# 32u4_board.net
KiCad netlist of a schematic drawn in EAGLE
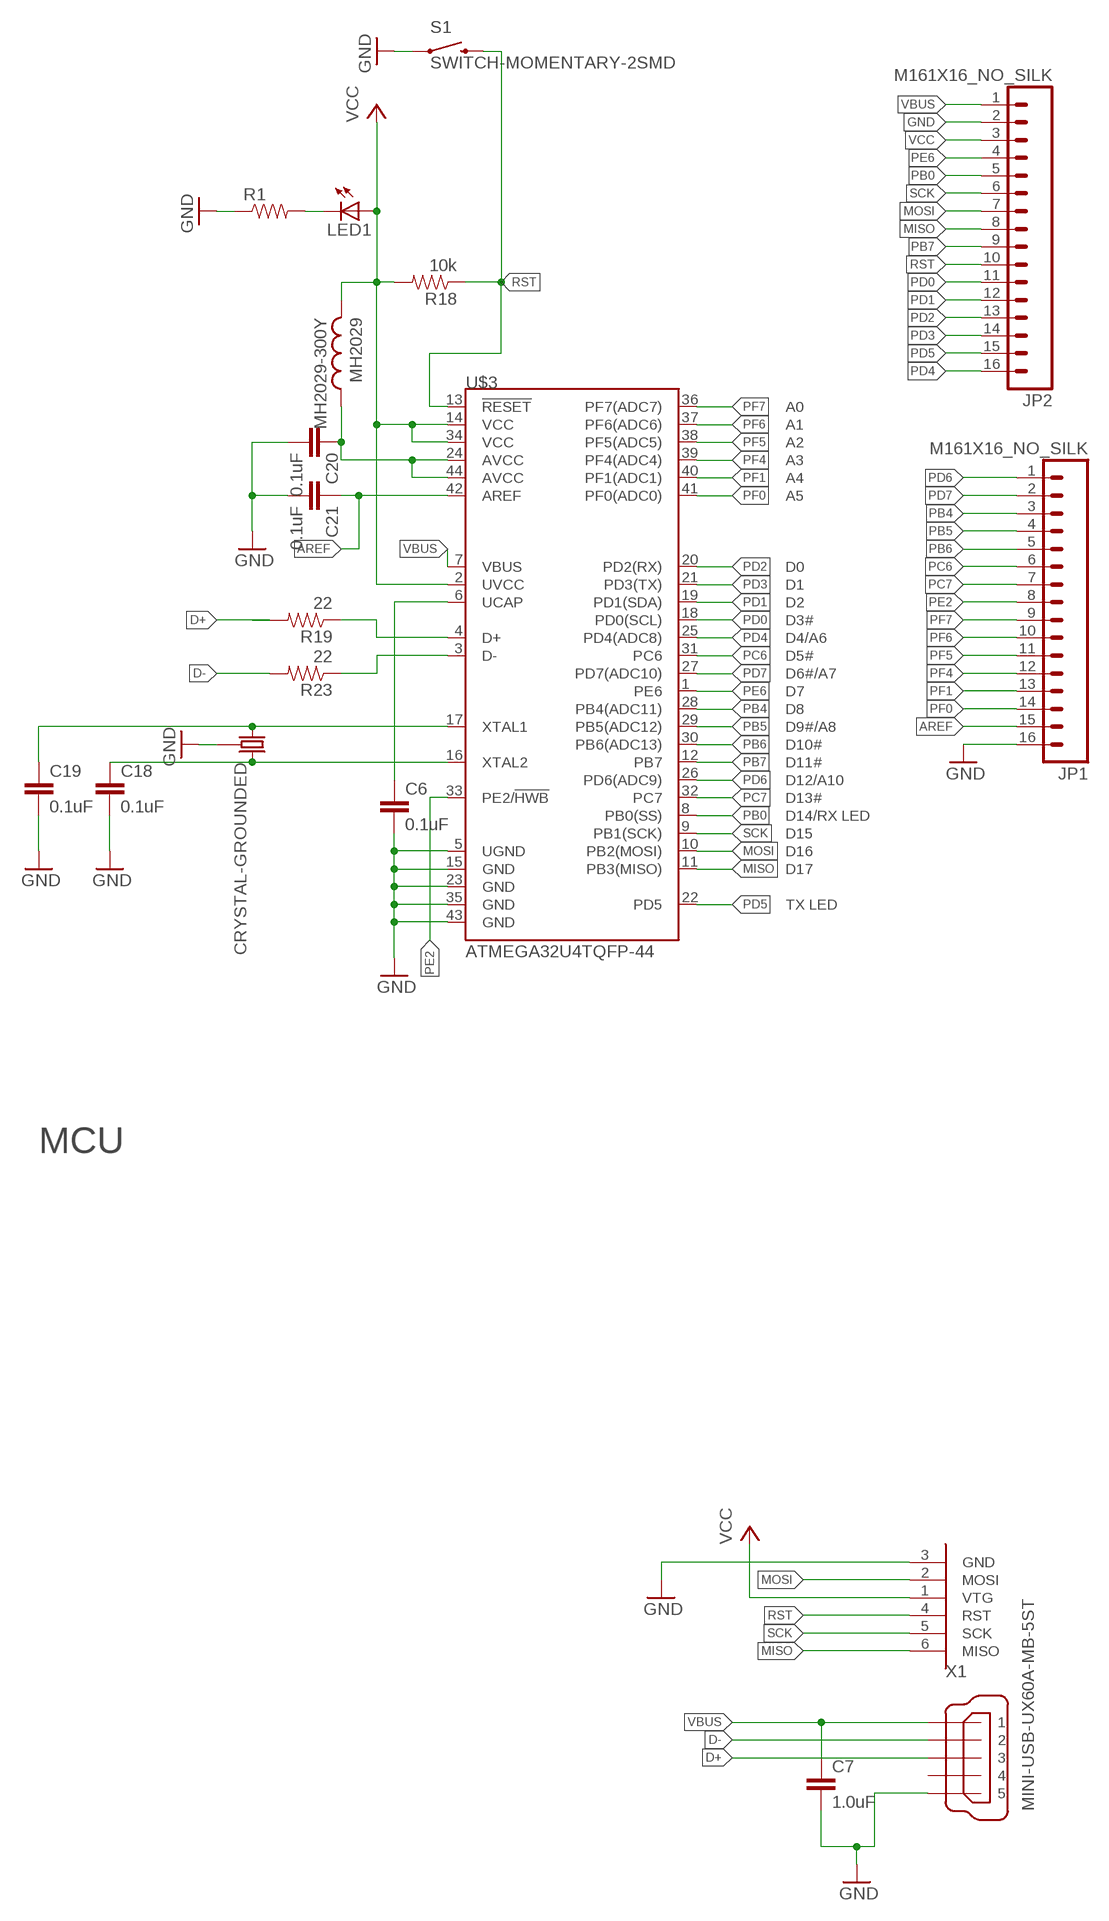
[diagram p0: schematic, sheet 1]

(export (version "E")
  (design (tool "Eeschema 10.0.6"))
  (components
    (comp (ref "C6")
      (value "0.1uF")
      (footprint "eagle-import:0603-CAP")
      (libsource (lib "eagle-import") (part "0.1UF-25V(+80/-20%)(0603)"))
    )
    (comp (ref "C7")
      (value "1.0uF")
      (footprint "eagle-import:0603-CAP")
      (libsource (lib "eagle-import") (part "1.0UF-16V-10%(0603)"))
    )
    (comp (ref "C18")
      (value "0.1uF")
      (footprint "eagle-import:0603-CAP")
      (libsource (lib "eagle-import") (part "0.1UF-25V(+80/-20%)(0603)"))
    )
    (comp (ref "C19")
      (value "0.1uF")
      (footprint "eagle-import:0603-CAP")
      (libsource (lib "eagle-import") (part "0.1UF-25V(+80/-20%)(0603)"))
    )
    (comp (ref "C20")
      (value "0.1uF")
      (footprint "eagle-import:0603-CAP")
      (libsource (lib "eagle-import") (part "0.1UF-25V(+80/-20%)(0603)"))
    )
    (comp (ref "C21")
      (value "0.1uF")
      (footprint "eagle-import:0603-CAP")
      (libsource (lib "eagle-import") (part "0.1UF-25V(+80/-20%)(0603)"))
    )
    (comp (ref "JP1")
      (value "M161X16_NO_SILK")
      (footprint "eagle-import:1X16_NO_SILK")
      (libsource (lib "eagle-import") (part "M161X16_NO_SILK"))
    )
    (comp (ref "JP2")
      (value "M161X16_NO_SILK")
      (footprint "eagle-import:1X16_NO_SILK")
      (libsource (lib "eagle-import") (part "M161X16_NO_SILK"))
    )
    (comp (ref "LED1")
      (value "LEDCHIPLED_0603")
      (footprint "eagle-import:CHIPLED_0603")
      (libsource (lib "eagle-import") (part "LEDCHIPLED_0603"))
    )
    (comp (ref "MH2029")
      (value "MH2029-300Y")
      (footprint "eagle-import:L2012C")
      (libsource (lib "eagle-import") (part "L-USL2012C"))
    )
    (comp (ref "R1")
      (value "RESISTOR0603")
      (footprint "eagle-import:0603-RES")
      (libsource (lib "eagle-import") (part "RESISTOR0603"))
    )
    (comp (ref "R18")
      (value "10k")
      (footprint "eagle-import:0603-RES")
      (libsource (lib "eagle-import") (part "RESISTOR0603-RES"))
    )
    (comp (ref "R19")
      (value "22")
      (footprint "eagle-import:0603-RES")
      (libsource (lib "eagle-import") (part "RESISTOR0603-RES"))
    )
    (comp (ref "R23")
      (value "22")
      (footprint "eagle-import:0603-RES")
      (libsource (lib "eagle-import") (part "RESISTOR0603-RES"))
    )
    (comp (ref "S1")
      (value "SWITCH-MOMENTARY-2SMD")
      (footprint "eagle-import:TACTILE_SWITCH_SMD")
      (libsource (lib "eagle-import") (part "SWITCH-MOMENTARY-2SMD"))
    )
    (comp (ref "U$2")
      (value "ICSP_SMD")
      (footprint "eagle-import:ICSP")
      (libsource (lib "eagle-import") (part "ICSP_SMD"))
    )
    (comp (ref "U$3")
      (value "ATMEGA32U4TQFP-44")
      (footprint "eagle-import:TQFP44")
      (libsource (lib "eagle-import") (part "ATMEGA32U4TQFP-44"))
    )
    (comp (ref "U$4")
      (value "CRYSTAL-GROUNDED")
      (footprint "eagle-import:CRYSTAL-SMD-5X3")
      (libsource (lib "eagle-import") (part "CRYSTAL-GROUNDED"))
    )
    (comp (ref "X1")
      (value "MINI-USB-UX60A-MB-5ST")
      (footprint "eagle-import:UX60A-MB-5ST")
      (libsource (lib "eagle-import") (part "MINI-USB-UX60A-MB-5ST"))
    )
  )
  (nets
    (net (code "1") (name "AREF") (class "Default")
      (node (ref "C21") (pin "1") (pinfunction "1_1") (pintype "passive"))
      (node (ref "JP1") (pin "15") (pinfunction "15_15") (pintype "passive"))
      (node (ref "U$3") (pin "42") (pinfunction "AREF_42") (pintype "bidirectional"))
    )
    (net (code "2") (name "D+") (class "Default")
      (node (ref "R19") (pin "2") (pinfunction "2_2") (pintype "passive"))
      (node (ref "X1") (pin "3") (pinfunction "3_3") (pintype "input"))
    )
    (net (code "3") (name "D-") (class "Default")
      (node (ref "R23") (pin "2") (pinfunction "2_2") (pintype "passive"))
      (node (ref "X1") (pin "2") (pinfunction "2_2") (pintype "input"))
    )
    (net (code "4") (name "GND") (class "Default")
      (node (ref "C18") (pin "2") (pinfunction "2_2") (pintype "passive"))
      (node (ref "C19") (pin "2") (pinfunction "2_2") (pintype "passive"))
      (node (ref "C20") (pin "2") (pinfunction "2_2") (pintype "passive"))
      (node (ref "C21") (pin "2") (pinfunction "2_2") (pintype "passive"))
      (node (ref "C6") (pin "2") (pinfunction "2_2") (pintype "passive"))
      (node (ref "C7") (pin "2") (pinfunction "2_2") (pintype "passive"))
      (node (ref "JP1") (pin "16") (pinfunction "16_16") (pintype "passive"))
      (node (ref "JP2") (pin "2") (pinfunction "2_2") (pintype "passive"))
      (node (ref "R1") (pin "1") (pinfunction "1_1") (pintype "passive"))
      (node (ref "S1") (pin "1") (pinfunction "1_1") (pintype "passive"))
      (node (ref "U$2") (pin "3") (pinfunction "GND_3") (pintype "bidirectional"))
      (node (ref "U$3") (pin "15") (pinfunction "GND_15") (pintype "bidirectional"))
      (node (ref "U$3") (pin "23") (pinfunction "GND_23") (pintype "bidirectional"))
      (node (ref "U$3") (pin "35") (pinfunction "GND_35") (pintype "bidirectional"))
      (node (ref "U$3") (pin "43") (pinfunction "GND_43") (pintype "bidirectional"))
      (node (ref "U$3") (pin "5") (pinfunction "UGND_5") (pintype "bidirectional"))
      (node (ref "U$4") (pin "2") (pinfunction "3_2") (pintype "passive"))
      (node (ref "U$4") (pin "4") (pinfunction "3_4") (pintype "passive"))
      (node (ref "X1") (pin "5") (pinfunction "5_5") (pintype "input"))
    )
    (net (code "5") (name "MISO") (class "Default")
      (node (ref "JP2") (pin "8") (pinfunction "8_8") (pintype "passive"))
      (node (ref "U$2") (pin "6") (pinfunction "MISO_6") (pintype "bidirectional"))
      (node (ref "U$3") (pin "11") (pinfunction "PB3(MISO)_11") (pintype "bidirectional"))
    )
    (net (code "6") (name "MOSI") (class "Default")
      (node (ref "JP2") (pin "7") (pinfunction "7_7") (pintype "passive"))
      (node (ref "U$2") (pin "2") (pinfunction "MOSI_2") (pintype "bidirectional"))
      (node (ref "U$3") (pin "10") (pinfunction "PB2(MOSI)_10") (pintype "bidirectional"))
    )
    (net (code "7") (name "Net-(C20-Pad1)") (class "Default")
      (node (ref "C20") (pin "1") (pinfunction "1_1") (pintype "passive"))
      (node (ref "MH2029") (pin "1") (pinfunction "1_1") (pintype "passive"))
      (node (ref "U$3") (pin "24") (pinfunction "AVCC_24") (pintype "bidirectional"))
      (node (ref "U$3") (pin "44") (pinfunction "AVCC_44") (pintype "bidirectional"))
    )
    (net (code "8") (name "Net-(LED1-PadC)") (class "Default")
      (node (ref "LED1") (pin "C") (pinfunction "C_C") (pintype "passive"))
      (node (ref "R1") (pin "2") (pinfunction "2_2") (pintype "passive"))
    )
    (net (code "9") (name "Net-(U$3-D+)") (class "Default")
      (node (ref "R19") (pin "1") (pinfunction "1_1") (pintype "passive"))
      (node (ref "U$3") (pin "4") (pinfunction "D+_4") (pintype "bidirectional"))
    )
    (net (code "10") (name "Net-(U$3-D-)") (class "Default")
      (node (ref "R23") (pin "1") (pinfunction "1_1") (pintype "passive"))
      (node (ref "U$3") (pin "3") (pinfunction "D-_3") (pintype "bidirectional"))
    )
    (net (code "11") (name "Net-(U$3-UCAP)") (class "Default")
      (node (ref "C6") (pin "1") (pinfunction "1_1") (pintype "passive"))
      (node (ref "U$3") (pin "6") (pinfunction "UCAP_6") (pintype "bidirectional"))
    )
    (net (code "12") (name "Net-(U$3-XTAL1)") (class "Default")
      (node (ref "C19") (pin "1") (pinfunction "1_1") (pintype "passive"))
      (node (ref "U$3") (pin "17") (pinfunction "XTAL1_17") (pintype "bidirectional"))
      (node (ref "U$4") (pin "3") (pinfunction "1_3") (pintype "passive"))
    )
    (net (code "13") (name "Net-(U$3-XTAL2)") (class "Default")
      (node (ref "C18") (pin "1") (pinfunction "1_1") (pintype "passive"))
      (node (ref "U$3") (pin "16") (pinfunction "XTAL2_16") (pintype "bidirectional"))
      (node (ref "U$4") (pin "1") (pinfunction "2_1") (pintype "passive"))
    )
    (net (code "14") (name "PB0") (class "Default")
      (node (ref "JP2") (pin "5") (pinfunction "5_5") (pintype "passive"))
      (node (ref "U$3") (pin "8") (pinfunction "PB0(SS)_8") (pintype "bidirectional"))
    )
    (net (code "15") (name "PB4") (class "Default")
      (node (ref "JP1") (pin "3") (pinfunction "3_3") (pintype "passive"))
      (node (ref "U$3") (pin "28") (pinfunction "PB4(ADC11)_28") (pintype "bidirectional"))
    )
    (net (code "16") (name "PB5") (class "Default")
      (node (ref "JP1") (pin "4") (pinfunction "4_4") (pintype "passive"))
      (node (ref "U$3") (pin "29") (pinfunction "PB5(ADC12)_29") (pintype "bidirectional"))
    )
    (net (code "17") (name "PB6") (class "Default")
      (node (ref "JP1") (pin "5") (pinfunction "5_5") (pintype "passive"))
      (node (ref "U$3") (pin "30") (pinfunction "PB6(ADC13)_30") (pintype "bidirectional"))
    )
    (net (code "18") (name "PB7") (class "Default")
      (node (ref "JP2") (pin "9") (pinfunction "9_9") (pintype "passive"))
      (node (ref "U$3") (pin "12") (pinfunction "PB7_12") (pintype "bidirectional"))
    )
    (net (code "19") (name "PC6") (class "Default")
      (node (ref "JP1") (pin "6") (pinfunction "6_6") (pintype "passive"))
      (node (ref "U$3") (pin "31") (pinfunction "PC6_31") (pintype "bidirectional"))
    )
    (net (code "20") (name "PC7") (class "Default")
      (node (ref "JP1") (pin "7") (pinfunction "7_7") (pintype "passive"))
      (node (ref "U$3") (pin "32") (pinfunction "PC7_32") (pintype "bidirectional"))
    )
    (net (code "21") (name "PD0") (class "Default")
      (node (ref "JP2") (pin "11") (pinfunction "11_11") (pintype "passive"))
      (node (ref "U$3") (pin "18") (pinfunction "PD0(SCL)_18") (pintype "bidirectional"))
    )
    (net (code "22") (name "PD1") (class "Default")
      (node (ref "JP2") (pin "12") (pinfunction "12_12") (pintype "passive"))
      (node (ref "U$3") (pin "19") (pinfunction "PD1(SDA)_19") (pintype "bidirectional"))
    )
    (net (code "23") (name "PD2") (class "Default")
      (node (ref "JP2") (pin "13") (pinfunction "13_13") (pintype "passive"))
      (node (ref "U$3") (pin "20") (pinfunction "PD2(RX)_20") (pintype "bidirectional"))
    )
    (net (code "24") (name "PD3") (class "Default")
      (node (ref "JP2") (pin "14") (pinfunction "14_14") (pintype "passive"))
      (node (ref "U$3") (pin "21") (pinfunction "PD3(TX)_21") (pintype "bidirectional"))
    )
    (net (code "25") (name "PD4") (class "Default")
      (node (ref "JP2") (pin "16") (pinfunction "16_16") (pintype "passive"))
      (node (ref "U$3") (pin "25") (pinfunction "PD4(ADC8)_25") (pintype "bidirectional"))
    )
    (net (code "26") (name "PD5") (class "Default")
      (node (ref "JP2") (pin "15") (pinfunction "15_15") (pintype "passive"))
      (node (ref "U$3") (pin "22") (pinfunction "PD5_22") (pintype "bidirectional"))
    )
    (net (code "27") (name "PD6") (class "Default")
      (node (ref "JP1") (pin "1") (pinfunction "1_1") (pintype "passive"))
      (node (ref "U$3") (pin "26") (pinfunction "PD6(ADC9)_26") (pintype "bidirectional"))
    )
    (net (code "28") (name "PD7") (class "Default")
      (node (ref "JP1") (pin "2") (pinfunction "2_2") (pintype "passive"))
      (node (ref "U$3") (pin "27") (pinfunction "PD7(ADC10)_27") (pintype "bidirectional"))
    )
    (net (code "29") (name "PE2") (class "Default")
      (node (ref "JP1") (pin "8") (pinfunction "8_8") (pintype "passive"))
      (node (ref "U$3") (pin "33") (pinfunction "PE2/~{HWB}_33") (pintype "bidirectional"))
    )
    (net (code "30") (name "PE6") (class "Default")
      (node (ref "JP2") (pin "4") (pinfunction "4_4") (pintype "passive"))
      (node (ref "U$3") (pin "1") (pinfunction "PE6_1") (pintype "bidirectional"))
    )
    (net (code "31") (name "PF0") (class "Default")
      (node (ref "JP1") (pin "14") (pinfunction "14_14") (pintype "passive"))
      (node (ref "U$3") (pin "41") (pinfunction "PF0(ADC0)_41") (pintype "bidirectional"))
    )
    (net (code "32") (name "PF1") (class "Default")
      (node (ref "JP1") (pin "13") (pinfunction "13_13") (pintype "passive"))
      (node (ref "U$3") (pin "40") (pinfunction "PF1(ADC1)_40") (pintype "bidirectional"))
    )
    (net (code "33") (name "PF4") (class "Default")
      (node (ref "JP1") (pin "12") (pinfunction "12_12") (pintype "passive"))
      (node (ref "U$3") (pin "39") (pinfunction "PF4(ADC4)_39") (pintype "bidirectional"))
    )
    (net (code "34") (name "PF5") (class "Default")
      (node (ref "JP1") (pin "11") (pinfunction "11_11") (pintype "passive"))
      (node (ref "U$3") (pin "38") (pinfunction "PF5(ADC5)_38") (pintype "bidirectional"))
    )
    (net (code "35") (name "PF6") (class "Default")
      (node (ref "JP1") (pin "10") (pinfunction "10_10") (pintype "passive"))
      (node (ref "U$3") (pin "37") (pinfunction "PF6(ADC6)_37") (pintype "bidirectional"))
    )
    (net (code "36") (name "PF7") (class "Default")
      (node (ref "JP1") (pin "9") (pinfunction "9_9") (pintype "passive"))
      (node (ref "U$3") (pin "36") (pinfunction "PF7(ADC7)_36") (pintype "bidirectional"))
    )
    (net (code "37") (name "RST") (class "Default")
      (node (ref "JP2") (pin "10") (pinfunction "10_10") (pintype "passive"))
      (node (ref "R18") (pin "1") (pinfunction "1_1") (pintype "passive"))
      (node (ref "S1") (pin "3") (pinfunction "2_3") (pintype "passive"))
      (node (ref "U$2") (pin "4") (pinfunction "RST_4") (pintype "bidirectional"))
      (node (ref "U$3") (pin "13") (pinfunction "~{RESET}_13") (pintype "bidirectional"))
    )
    (net (code "38") (name "SCK") (class "Default")
      (node (ref "JP2") (pin "6") (pinfunction "6_6") (pintype "passive"))
      (node (ref "U$2") (pin "5") (pinfunction "SCK_5") (pintype "bidirectional"))
      (node (ref "U$3") (pin "9") (pinfunction "PB1(SCK)_9") (pintype "bidirectional"))
    )
    (net (code "39") (name "VBUS") (class "Default")
      (node (ref "C7") (pin "1") (pinfunction "1_1") (pintype "passive"))
      (node (ref "JP2") (pin "1") (pinfunction "1_1") (pintype "passive"))
      (node (ref "U$3") (pin "7") (pinfunction "VBUS_7") (pintype "bidirectional"))
      (node (ref "X1") (pin "1") (pinfunction "1_1") (pintype "input"))
    )
    (net (code "40") (name "VCC") (class "Default")
      (node (ref "JP2") (pin "3") (pinfunction "3_3") (pintype "passive"))
      (node (ref "LED1") (pin "A") (pinfunction "A_A") (pintype "passive"))
      (node (ref "MH2029") (pin "2") (pinfunction "2_2") (pintype "passive"))
      (node (ref "R18") (pin "2") (pinfunction "2_2") (pintype "passive"))
      (node (ref "U$2") (pin "1") (pinfunction "VTG_1") (pintype "bidirectional"))
      (node (ref "U$3") (pin "14") (pinfunction "VCC_14") (pintype "bidirectional"))
      (node (ref "U$3") (pin "2") (pinfunction "UVCC_2") (pintype "bidirectional"))
      (node (ref "U$3") (pin "34") (pinfunction "VCC_34") (pintype "bidirectional"))
    )
    (net (code "41") (name "unconnected-(X1-Pad4)") (class "Default")
      (node (ref "X1") (pin "4") (pinfunction "4_4") (pintype "input"))
    )
  )
)
